# rocket_pack-basic.net
KiCad netlist of a schematic drawn in EAGLE
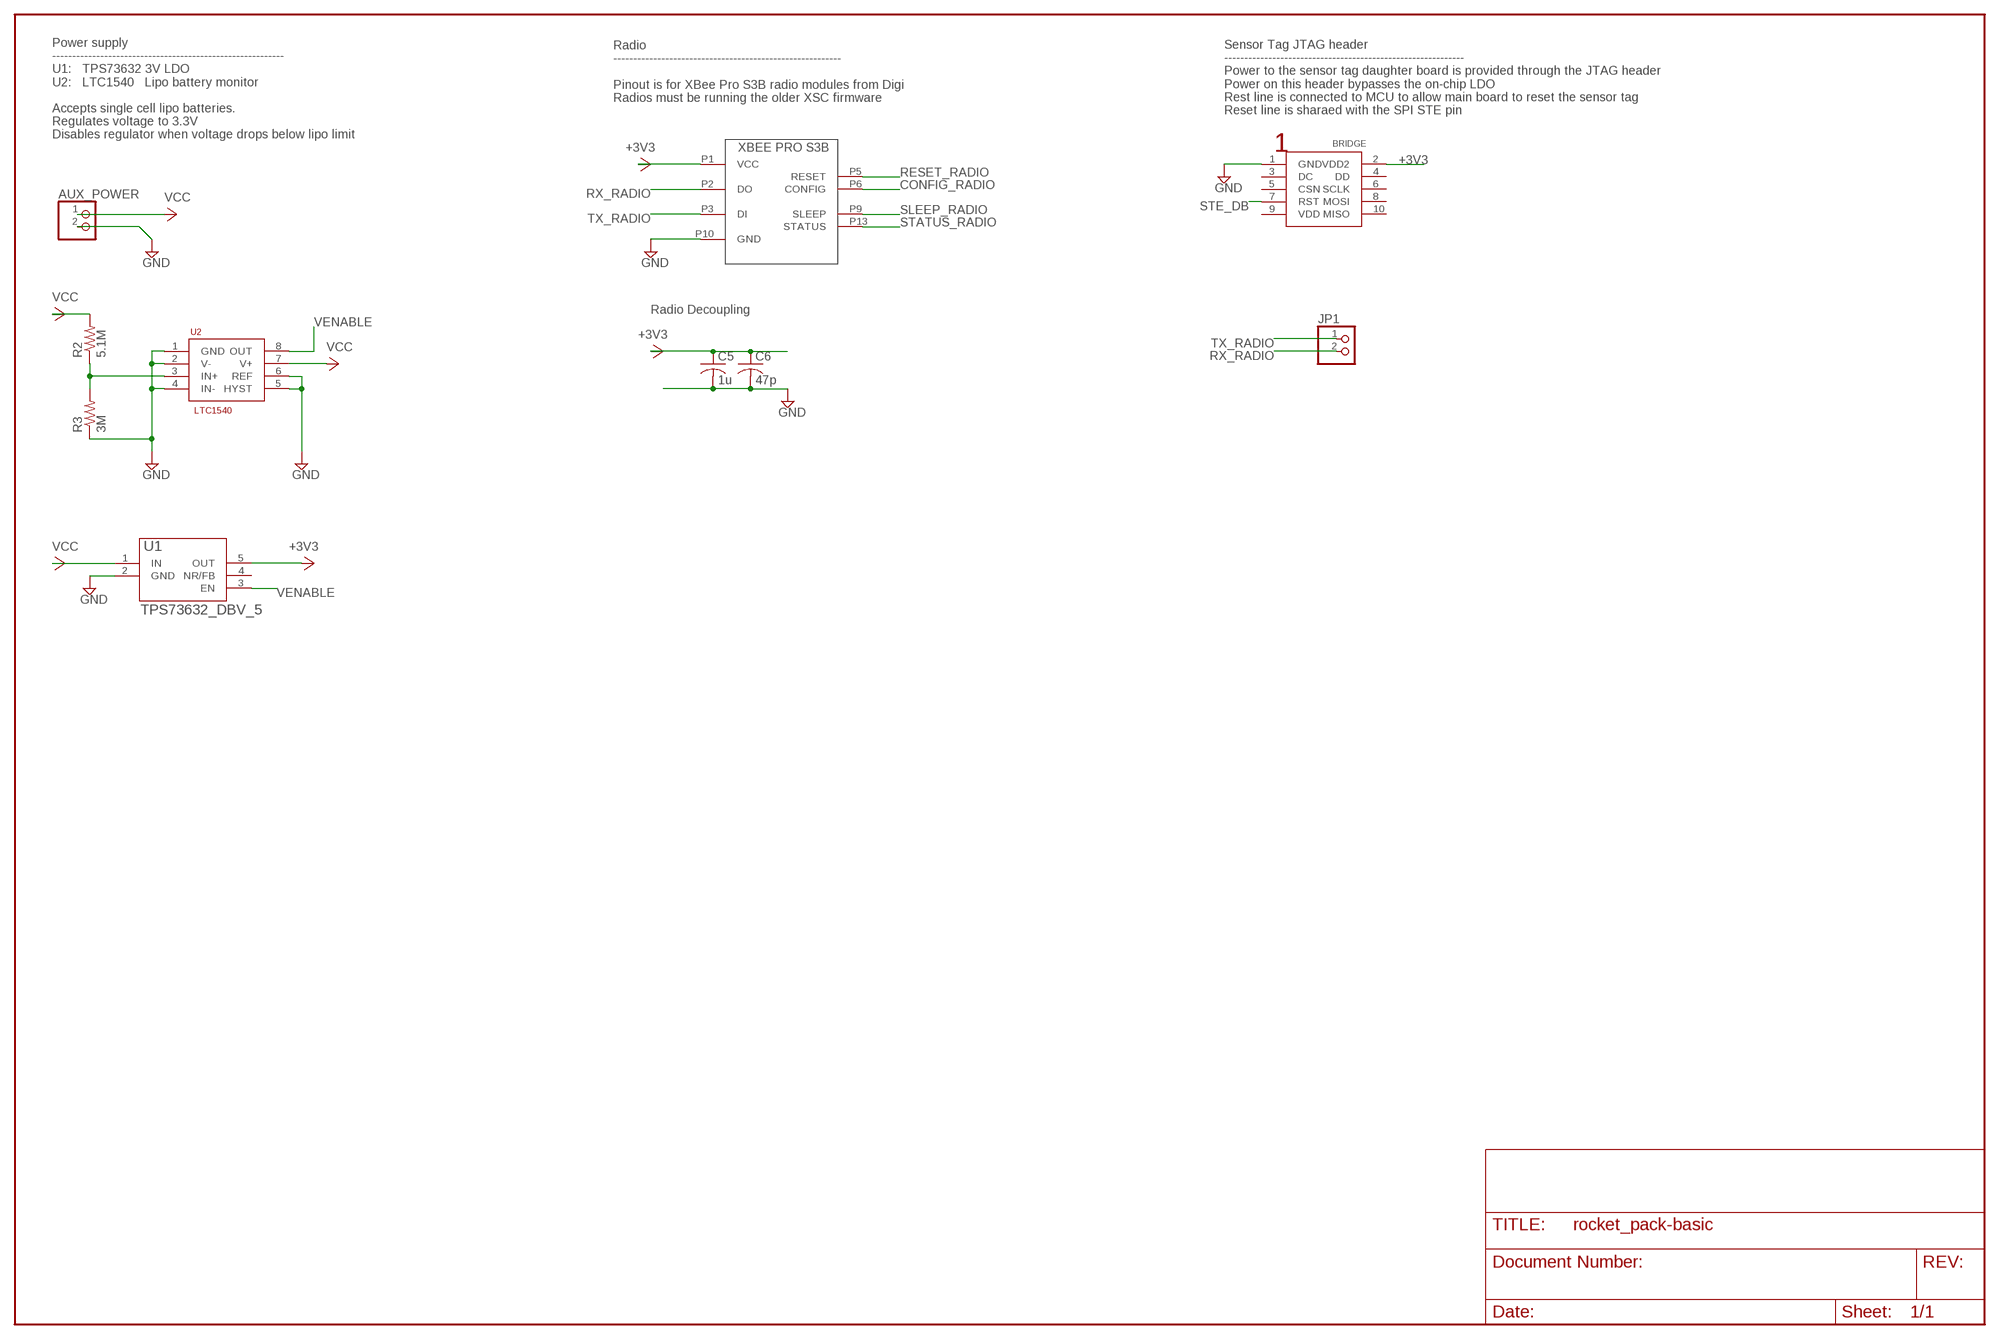
[diagram p0: schematic, sheet 1]

(export (version "E")
  (design (tool "Eeschema 10.0.6"))
  (components
    (comp (ref "AUX_POWER")
      (value "PINHD-1X2")
      (footprint "eagle-import:1X02")
      (libsource (lib "eagle-import") (part "PINHD-1X2"))
    )
    (comp (ref "BRIDGE")
      (value "CC-DEBUG")
      (footprint "eagle-import:2X5-1.27MM")
      (libsource (lib "eagle-import") (part "CC-DEBUG"))
    )
    (comp (ref "C5")
      (value "1u")
      (footprint "eagle-import:C1206")
      (libsource (lib "eagle-import") (part "C-USC1206"))
    )
    (comp (ref "C6")
      (value "47p")
      (footprint "eagle-import:C1206")
      (libsource (lib "eagle-import") (part "C-USC1206"))
    )
    (comp (ref "JP1")
      (value "PINHD-1X2/90")
      (footprint "eagle-import:1X02_90")
      (libsource (lib "eagle-import") (part "PINHD-1X2/90"))
    )
    (comp (ref "R2")
      (value "5.1M")
      (footprint "eagle-import:R1206")
      (fields (field (name "MPN") "MCPWR06FTEO5104"))
      (libsource (lib "eagle-import") (part "R-US_R1206"))
    )
    (comp (ref "R3")
      (value "3M")
      (footprint "eagle-import:R1206")
      (libsource (lib "eagle-import") (part "R-US_R1206"))
    )
    (comp (ref "U$1")
      (value "XBEE_PRO_S3B")
      (footprint "eagle-import:PRO_S3B")
      (libsource (lib "eagle-import") (part "XBEE_PRO_S3B"))
    )
    (comp (ref "U1")
      (value "TPS73632_DBV_5")
      (footprint "eagle-import:DBV5")
      (fields
        (field (name "GENERIC_PART_NUMBER") "TPS73632")
        (field (name "MANUFACTURER") "Texas Instruments")
        (field (name "MANUFACTURER_PART_NUMBER") "tps73632_dbv_5")
      )
      (libsource (lib "eagle-import") (part "TPS73632_DBV_5"))
    )
    (comp (ref "U2")
      (value "LTC1540")
      (footprint "eagle-import:S8")
      (fields (field (name "MPN") "LTC1540CMS8#PBF"))
      (libsource (lib "eagle-import") (part "LTC1540"))
    )
  )
  (nets
    (net (code "1") (name "+3V3") (class "Default")
      (node (ref "BRIDGE") (pin "2") (pinfunction "VDD2_2") (pintype "bidirectional"))
      (node (ref "C5") (pin "1") (pinfunction "1_1") (pintype "passive"))
      (node (ref "C6") (pin "1") (pinfunction "1_1") (pintype "passive"))
      (node (ref "U$1") (pin "P1") (pinfunction "VCC_P1") (pintype "bidirectional"))
      (node (ref "U1") (pin "5") (pinfunction "OUT_5") (pintype "output"))
    )
    (net (code "2") (name "/CONFIG_RADIO") (class "Default")
      (node (ref "U$1") (pin "P6") (pinfunction "CONFIG_P6") (pintype "bidirectional"))
    )
    (net (code "3") (name "/RESET_RADIO") (class "Default")
      (node (ref "U$1") (pin "P5") (pinfunction "RESET_P5") (pintype "bidirectional"))
    )
    (net (code "4") (name "/RX_RADIO") (class "Default")
      (node (ref "JP1") (pin "2") (pinfunction "2_2") (pintype "passive"))
      (node (ref "U$1") (pin "P2") (pinfunction "DO_P2") (pintype "bidirectional"))
    )
    (net (code "5") (name "/SLEEP_RADIO") (class "Default")
      (node (ref "U$1") (pin "P9") (pinfunction "SLEEP_P9") (pintype "bidirectional"))
    )
    (net (code "6") (name "/STATUS_RADIO") (class "Default")
      (node (ref "U$1") (pin "P13") (pinfunction "STATUS_P13") (pintype "bidirectional"))
    )
    (net (code "7") (name "/STE_DB") (class "Default")
      (node (ref "BRIDGE") (pin "7") (pinfunction "RST_7") (pintype "bidirectional"))
    )
    (net (code "8") (name "/TX_RADIO") (class "Default")
      (node (ref "JP1") (pin "1") (pinfunction "1_1") (pintype "passive"))
      (node (ref "U$1") (pin "P3") (pinfunction "DI_P3") (pintype "bidirectional"))
    )
    (net (code "9") (name "/VENABLE") (class "Default")
      (node (ref "U1") (pin "3") (pinfunction "EN_3") (pintype "passive"))
      (node (ref "U2") (pin "8") (pinfunction "OUT_8") (pintype "bidirectional"))
    )
    (net (code "10") (name "GND") (class "Default")
      (node (ref "AUX_POWER") (pin "2") (pinfunction "2_2") (pintype "passive"))
      (node (ref "BRIDGE") (pin "1") (pinfunction "GND_1") (pintype "bidirectional"))
      (node (ref "C5") (pin "2") (pinfunction "2_2") (pintype "passive"))
      (node (ref "C6") (pin "2") (pinfunction "2_2") (pintype "passive"))
      (node (ref "R3") (pin "1") (pinfunction "1_1") (pintype "passive"))
      (node (ref "U$1") (pin "P10") (pinfunction "GND_P10") (pintype "bidirectional"))
      (node (ref "U1") (pin "2") (pinfunction "GND_2") (pintype "power_in"))
      (node (ref "U2") (pin "1") (pinfunction "GND_1") (pintype "bidirectional"))
      (node (ref "U2") (pin "2") (pinfunction "V-_2") (pintype "bidirectional"))
      (node (ref "U2") (pin "4") (pinfunction "IN-_4") (pintype "bidirectional"))
      (node (ref "U2") (pin "5") (pinfunction "HYST_5") (pintype "bidirectional"))
      (node (ref "U2") (pin "6") (pinfunction "REF_6") (pintype "bidirectional"))
    )
    (net (code "11") (name "Net-(U2-IN+)") (class "Default")
      (node (ref "R2") (pin "1") (pinfunction "1_1") (pintype "passive"))
      (node (ref "R3") (pin "2") (pinfunction "2_2") (pintype "passive"))
      (node (ref "U2") (pin "3") (pinfunction "IN+_3") (pintype "bidirectional"))
    )
    (net (code "12") (name "VCC") (class "Default")
      (node (ref "AUX_POWER") (pin "1") (pinfunction "1_1") (pintype "passive"))
      (node (ref "R2") (pin "2") (pinfunction "2_2") (pintype "passive"))
      (node (ref "U1") (pin "1") (pinfunction "IN_1") (pintype "input"))
      (node (ref "U2") (pin "7") (pinfunction "V+_7") (pintype "bidirectional"))
    )
    (net (code "13") (name "unconnected-(BRIDGE-CSN-Pad5)") (class "Default")
      (node (ref "BRIDGE") (pin "5") (pinfunction "CSN_5") (pintype "bidirectional"))
    )
    (net (code "14") (name "unconnected-(BRIDGE-DC-Pad3)") (class "Default")
      (node (ref "BRIDGE") (pin "3") (pinfunction "DC_3") (pintype "bidirectional"))
    )
    (net (code "15") (name "unconnected-(BRIDGE-DD-Pad4)") (class "Default")
      (node (ref "BRIDGE") (pin "4") (pinfunction "DD_4") (pintype "bidirectional"))
    )
    (net (code "16") (name "unconnected-(BRIDGE-MISO-Pad10)") (class "Default")
      (node (ref "BRIDGE") (pin "10") (pinfunction "MISO_10") (pintype "bidirectional"))
    )
    (net (code "17") (name "unconnected-(BRIDGE-MOSI-Pad8)") (class "Default")
      (node (ref "BRIDGE") (pin "8") (pinfunction "MOSI_8") (pintype "bidirectional"))
    )
    (net (code "18") (name "unconnected-(BRIDGE-SCLK-Pad6)") (class "Default")
      (node (ref "BRIDGE") (pin "6") (pinfunction "SCLK_6") (pintype "bidirectional"))
    )
    (net (code "19") (name "unconnected-(BRIDGE-VDD-Pad9)") (class "Default")
      (node (ref "BRIDGE") (pin "9") (pinfunction "VDD_9") (pintype "bidirectional"))
    )
    (net (code "20") (name "unconnected-(U1-NR{slash}FB-Pad4)") (class "Default")
      (node (ref "U1") (pin "4") (pinfunction "NR/FB_4") (pintype "bidirectional"))
    )
  )
)
